# STM32_microcontroller_IOs.net
KiCad netlist of a schematic drawn in Altium Designer
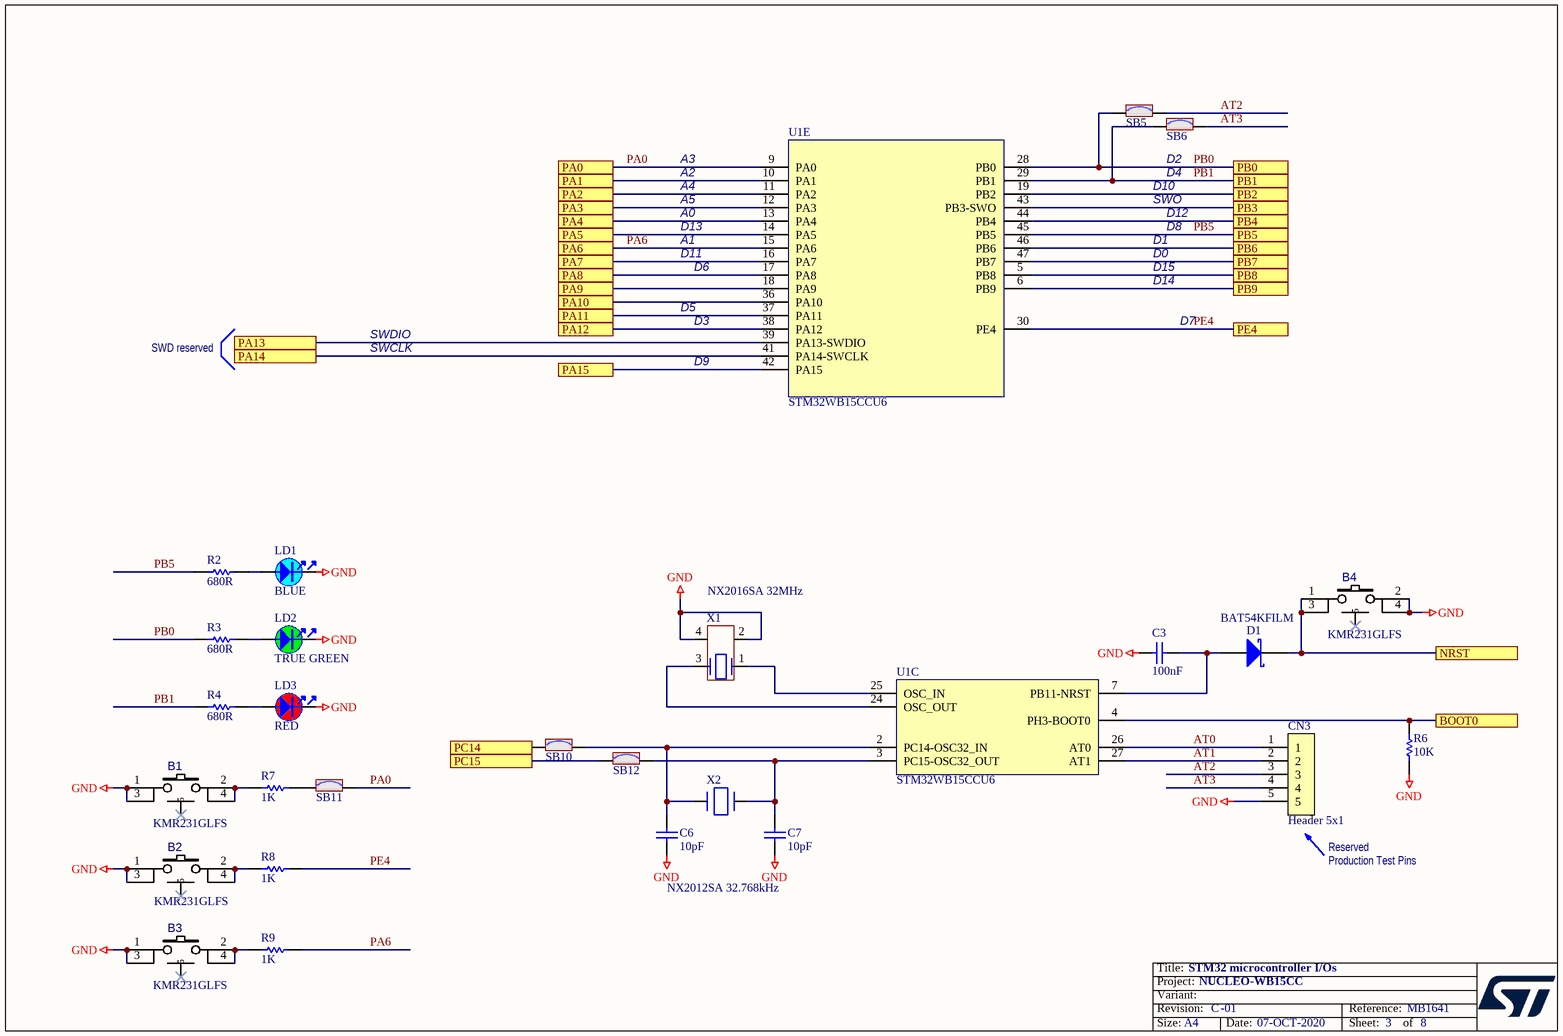
[diagram p0: STM32_microcontroller_IOs.SchDoc]

(export (version "E")
  (design (tool "Eeschema 10.0.6"))
  (components
    (comp (ref "B1")
      (value "KMR231GLFS")
      (footprint "SWI_C&K_Y78B23110FP__ITT_KMR231GLFS")
      (description "Microminiature Tact Switch for SMT - KMR 2 Series - 1.9 mm height")
      (fields (field (name "INTERNAL_PART_NUMBER") "MCD-01485") (field (name "MANUFACTURER") "C&K"))
      (libsource (lib "MCD_PARTS_database") (part "SW-PUSH-CMS_KMR2_BLACK"))
    )
    (comp (ref "B2")
      (value "KMR231GLFS")
      (footprint "SWI_C&K_Y78B23110FP__ITT_KMR231GLFS")
      (description "Microminiature Tact Switch for SMT - KMR 2 Series - 1.9 mm height")
      (fields (field (name "INTERNAL_PART_NUMBER") "MCD-01485") (field (name "MANUFACTURER") "C&K"))
      (libsource (lib "MCD_PARTS_database") (part "SW-PUSH-CMS_KMR2_BLACK"))
    )
    (comp (ref "B3")
      (value "KMR231GLFS")
      (footprint "SWI_C&K_Y78B23110FP__ITT_KMR231GLFS")
      (description "Microminiature Tact Switch for SMT - KMR 2 Series - 1.9 mm height")
      (fields (field (name "INTERNAL_PART_NUMBER") "MCD-01485") (field (name "MANUFACTURER") "C&K"))
      (libsource (lib "MCD_PARTS_database") (part "SW-PUSH-CMS_KMR2_BLACK"))
    )
    (comp (ref "B4")
      (value "KMR231GLFS")
      (footprint "SWI_C&K_Y78B23110FP__ITT_KMR231GLFS")
      (description "Microminiature Tact Switch for SMT - KMR 2 Series - 1.9 mm height")
      (fields (field (name "INTERNAL_PART_NUMBER") "MCD-01485") (field (name "MANUFACTURER") "C&K"))
      (libsource (lib "MCD_PARTS_database") (part "SW-PUSH-CMS_KMR2_BLACK"))
    )
    (comp (ref "C3")
      (value "100nF")
      (footprint "C0402")
      (description "Capacitor, MLCC, 100nF, 16V, X7R, +/-10%, 0402, T=0.5mm")
      (fields
        (field (name "INTERNAL_PART_NUMBER") "MCD-00006")
        (field (name "MANUFACTURER_PART_NUMBER") "CC0402KRX7R7BB104")
      )
      (libsource (lib "MCD_PARTS_database") (part "Capacitor"))
    )
    (comp (ref "C6")
      (value "10pF")
      (footprint "C0402")
      (description "Capacitor, MLCC, 10pF, 50V, NPO, +/-5%, 0402, T=0,5mm")
      (fields
        (field (name "INTERNAL_PART_NUMBER") "MCD-00015")
        (field (name "MANUFACTURER_PART_NUMBER") "CC0402JRNPO9BN100")
      )
      (libsource (lib "MCD_PARTS_database") (part "Capacitor"))
    )
    (comp (ref "C7")
      (value "10pF")
      (footprint "C0402")
      (description "Capacitor, MLCC, 10pF, 50V, NPO, +/-5%, 0402, T=0,5mm")
      (fields
        (field (name "INTERNAL_PART_NUMBER") "MCD-00015")
        (field (name "MANUFACTURER_PART_NUMBER") "CC0402JRNPO9BN100")
      )
      (libsource (lib "MCD_PARTS_database") (part "Capacitor"))
    )
    (comp (ref "CN3")
      (value "Header 5x1")
      (footprint "CON_SAMTEC_TSW-105-07-X-S")
      (description "Header, 5x1, 2,54mm, VR, TH, Height 5.84mm/2.54mm")
      (fields
        (field (name "INTERNAL_PART_NUMBER") "MCD-02060")
        (field (name "MANUFACTURER_PART_NUMBER") "TSW-105-07-G-S")
      )
      (libsource (lib "MCD_PARTS_database") (part "Header 5x1"))
    )
    (comp (ref "D1")
      (value "BAT54KFILM")
      (footprint "DIO_SOD523_1A_2K")
      (description "Small signal Schottky diodes")
      (fields
        (field (name "INTERNAL_PART_NUMBER") "MCD-01677")
        (field (name "MANUFACTURER") "STMICROELECTRONICS")
      )
      (libsource (lib "MCD_PARTS_database") (part "SCHOTTKY_1A_2K"))
    )
    (comp (ref "LD1")
      (value "BLUE")
      (footprint "LED_0603_VISHAY_VLMB1300-GS08_BLUE_1A2K_H0P8")
      (description "LED Blue, 0603 SMD, 3.3 V Forward Voltage")
      (fields
        (field (name "INTERNAL_PART_NUMBER") "MCD-00584")
        (field (name "MANUFACTURER_PART_NUMBER") "VLMB1300-GS08")
      )
      (libsource (lib "MCD_PARTS_database") (part "LED_blue"))
    )
    (comp (ref "LD2")
      (value "TRUE GREEN")
      (footprint "LED_0603_VISHAY_VLMTG1300-GS08_GREEN_1A2K_H0P8")
      (description "LED Green, 0603 SMD, Fw Voltage = 2.8V - 3.6V")
      (fields
        (field (name "INTERNAL_PART_NUMBER") "MCD-00589")
        (field (name "MANUFACTURER_PART_NUMBER") "VLMTG1300-GS08")
      )
      (libsource (lib "MCD_PARTS_database") (part "LED_green"))
    )
    (comp (ref "LD3")
      (value "RED")
      (footprint "LED_0603_VISHAY_VLMS1300-GS08_RED_1A2K_H0P8")
      (description "LED Red, 0603 SMD, 2V Forward Voltage")
      (fields
        (field (name "INTERNAL_PART_NUMBER") "MCD-00587")
        (field (name "MANUFACTURER_PART_NUMBER") "VLMS1300-GS08")
      )
      (libsource (lib "MCD_PARTS_database") (part "LED_red"))
    )
    (comp (ref "R2")
      (value "680R")
      (footprint "R0402")
      (description "Resistor,680R,0402,1%,1/16W")
      (fields
        (field (name "INTERNAL_PART_NUMBER") "MCD-00507")
        (field (name "MANUFACTURER_PART_NUMBER") "RC0402FR-07680RL")
      )
      (libsource (lib "MCD_PARTS_database") (part "Resistor"))
    )
    (comp (ref "R3")
      (value "680R")
      (footprint "R0402")
      (description "Resistor,680R,0402,1%,1/16W")
      (fields
        (field (name "INTERNAL_PART_NUMBER") "MCD-00507")
        (field (name "MANUFACTURER_PART_NUMBER") "RC0402FR-07680RL")
      )
      (libsource (lib "MCD_PARTS_database") (part "Resistor"))
    )
    (comp (ref "R4")
      (value "680R")
      (footprint "R0402")
      (description "Resistor,680R,0402,1%,1/16W")
      (fields
        (field (name "INTERNAL_PART_NUMBER") "MCD-00507")
        (field (name "MANUFACTURER_PART_NUMBER") "RC0402FR-07680RL")
      )
      (libsource (lib "MCD_PARTS_database") (part "Resistor"))
    )
    (comp (ref "R6")
      (value "10K")
      (footprint "R0402")
      (description "Resistor,10K,0402,1%,1/16W")
      (fields
        (field (name "INTERNAL_PART_NUMBER") "MCD-00053")
        (field (name "MANUFACTURER_PART_NUMBER") "RC0402FR-0710KL")
      )
      (libsource (lib "MCD_PARTS_database") (part "Resistor"))
    )
    (comp (ref "R7")
      (value "1K")
      (footprint "R0402")
      (description "Resistor,1K,0402,1%,1/16W")
      (fields
        (field (name "INTERNAL_PART_NUMBER") "MCD-00061")
        (field (name "MANUFACTURER_PART_NUMBER") "RC0402FR-071KL")
      )
      (libsource (lib "MCD_PARTS_database") (part "Resistor"))
    )
    (comp (ref "R8")
      (value "1K")
      (footprint "R0402")
      (description "Resistor,1K,0402,1%,1/16W")
      (fields
        (field (name "INTERNAL_PART_NUMBER") "MCD-00061")
        (field (name "MANUFACTURER_PART_NUMBER") "RC0402FR-071KL")
      )
      (libsource (lib "MCD_PARTS_database") (part "Resistor"))
    )
    (comp (ref "R9")
      (value "1K")
      (footprint "R0402")
      (description "Resistor,1K,0402,1%,1/16W")
      (fields
        (field (name "INTERNAL_PART_NUMBER") "MCD-00061")
        (field (name "MANUFACTURER_PART_NUMBER") "RC0402FR-071KL")
      )
      (libsource (lib "MCD_PARTS_database") (part "Resistor"))
    )
    (comp (ref "SB5")
      (value "SB_ON")
      (footprint "SOLDER-BRIDGE_R0402-0R")
      (description "Solder Bridge 0402 ON")
      (fields
        (field (name "INTERNAL_PART_NUMBER") "MCD-01618")
        (field (name "MANUFACTURER_PART_NUMBER") "RC0402JR-070RL")
      )
      (libsource (lib "MCD_PARTS_database") (part "SB_ON"))
    )
    (comp (ref "SB6")
      (value "SB_ON")
      (footprint "SOLDER-BRIDGE_R0402-0R")
      (description "Solder Bridge 0402 ON")
      (fields
        (field (name "INTERNAL_PART_NUMBER") "MCD-01618")
        (field (name "MANUFACTURER_PART_NUMBER") "RC0402JR-070RL")
      )
      (libsource (lib "MCD_PARTS_database") (part "SB_ON"))
    )
    (comp (ref "SB10")
      (value "SB_ON")
      (footprint "SOLDER-BRIDGE_R0402-0R")
      (description "Solder Bridge 0402 ON")
      (fields
        (field (name "INTERNAL_PART_NUMBER") "MCD-01618")
        (field (name "MANUFACTURER_PART_NUMBER") "RC0402JR-070RL")
      )
      (libsource (lib "MCD_PARTS_database") (part "SB_ON"))
    )
    (comp (ref "SB11")
      (value "SB_ON")
      (footprint "SOLDER-BRIDGE_R0402-0R")
      (description "Solder Bridge 0402 ON")
      (fields
        (field (name "INTERNAL_PART_NUMBER") "MCD-01618")
        (field (name "MANUFACTURER_PART_NUMBER") "RC0402JR-070RL")
      )
      (libsource (lib "MCD_PARTS_database") (part "SB_ON"))
    )
    (comp (ref "SB12")
      (value "SB_ON")
      (footprint "SOLDER-BRIDGE_R0402-0R")
      (description "Solder Bridge 0402 ON")
      (fields
        (field (name "INTERNAL_PART_NUMBER") "MCD-01618")
        (field (name "MANUFACTURER_PART_NUMBER") "RC0402JR-070RL")
      )
      (libsource (lib "MCD_PARTS_database") (part "SB_ON"))
    )
    (comp (ref "U1")
      (value "STM32WB15CCU6")
      (footprint "ICC_UFQFPN48-EPAD_7X7_H0P55_P050")
      (fields
        (field (name "INTERNAL_PART_NUMBER") "MCD-02058")
        (field (name "MANUFACTURER") "STMICROELECTRONICS")
        (field (name "Comment") "STM32WB15_QFN48")
      )
      (libsource (lib "MCD_PARTS_database") (part "STM32WB15_QFN48"))
    )
    (comp (ref "X1")
      (value "NX2016SA 32MHz")
      (footprint "CRY_NX2016SA_4P")
      (description "Crystal 32MHz, 8pF, +-10ppm, 60ohms max, SMD")
      (fields
        (field (name "INTERNAL_PART_NUMBER") "MCD-01446")
        (field (name "MANUFACTURER_PART_NUMBER") "NX2016SA 32MHz EXS00A-CS06654")
      )
      (libsource (lib "MCD_PARTS_database") (part "XTAL_4_PINS"))
    )
    (comp (ref "X2")
      (value "NX2012SA 32.768kHz")
      (footprint "CRY_NX2012SA_2P")
      (description "Crystal 32.768kHz, 7pF, +-20ppm, 80Kohms max, SMD")
      (fields
        (field (name "INTERNAL_PART_NUMBER") "MCD-01445")
        (field (name "MANUFACTURER_PART_NUMBER") "NX2012SA 32.768kHz EXS00A-MU00389")
      )
      (libsource (lib "MCD_PARTS_database") (part "XTAL_2_PINS"))
    )
  )
  (nets
    (net (code "1") (name "/AT0") (class "Default")
      (node (ref "CN3") (pin "1") (pinfunction "1_1") (pintype "passive"))
      (node (ref "U1") (pin "26") (pinfunction "AT0_26") (pintype "passive"))
    )
    (net (code "2") (name "/AT1") (class "Default")
      (node (ref "CN3") (pin "2") (pinfunction "2_2") (pintype "passive"))
      (node (ref "U1") (pin "27") (pinfunction "AT1_27") (pintype "passive"))
    )
    (net (code "3") (name "/AT2") (class "Default")
      (node (ref "CN3") (pin "3") (pinfunction "3_3") (pintype "passive"))
      (node (ref "SB5") (pin "2") (pinfunction "2_2") (pintype "passive"))
    )
    (net (code "4") (name "/AT3") (class "Default")
      (node (ref "CN3") (pin "4") (pinfunction "4_4") (pintype "passive"))
      (node (ref "SB6") (pin "2") (pinfunction "2_2") (pintype "passive"))
    )
    (net (code "5") (name "/BOOT0") (class "Default")
      (node (ref "R6") (pin "2") (pinfunction "2_2") (pintype "passive"))
      (node (ref "U1") (pin "4") (pinfunction "PH3-BOOT0_4") (pintype "passive"))
    )
    (net (code "6") (name "/NRST") (class "Default")
      (node (ref "B4") (pin "1") (pinfunction "1_1") (pintype "passive"))
      (node (ref "B4") (pin "3") (pinfunction "3_3") (pintype "passive"))
      (node (ref "D1") (pin "2") (pinfunction "K_2") (pintype "passive"))
    )
    (net (code "7") (name "/PA0") (class "Default")
      (node (ref "SB11") (pin "2") (pinfunction "2_2") (pintype "passive"))
      (node (ref "U1") (pin "9") (pinfunction "PA0_9") (pintype "passive"))
    )
    (net (code "8") (name "/PA1") (class "Default")
      (node (ref "U1") (pin "10") (pinfunction "PA1_10") (pintype "passive"))
    )
    (net (code "9") (name "/PA2") (class "Default")
      (node (ref "U1") (pin "11") (pinfunction "PA2_11") (pintype "passive"))
    )
    (net (code "10") (name "/PA3") (class "Default")
      (node (ref "U1") (pin "12") (pinfunction "PA3_12") (pintype "passive"))
    )
    (net (code "11") (name "/PA4") (class "Default")
      (node (ref "U1") (pin "13") (pinfunction "PA4_13") (pintype "passive"))
    )
    (net (code "12") (name "/PA5") (class "Default")
      (node (ref "U1") (pin "14") (pinfunction "PA5_14") (pintype "passive"))
    )
    (net (code "13") (name "/PA6") (class "Default")
      (node (ref "R9") (pin "2") (pinfunction "2_2") (pintype "passive"))
      (node (ref "U1") (pin "15") (pinfunction "PA6_15") (pintype "passive"))
    )
    (net (code "14") (name "/PA7") (class "Default")
      (node (ref "U1") (pin "16") (pinfunction "PA7_16") (pintype "passive"))
    )
    (net (code "15") (name "/PA8") (class "Default")
      (node (ref "U1") (pin "17") (pinfunction "PA8_17") (pintype "passive"))
    )
    (net (code "16") (name "/PA9") (class "Default")
      (node (ref "U1") (pin "18") (pinfunction "PA9_18") (pintype "passive"))
    )
    (net (code "17") (name "/PA10") (class "Default")
      (node (ref "U1") (pin "36") (pinfunction "PA10_36") (pintype "passive"))
    )
    (net (code "18") (name "/PA11") (class "Default")
      (node (ref "U1") (pin "37") (pinfunction "PA11_37") (pintype "passive"))
    )
    (net (code "19") (name "/PA12") (class "Default")
      (node (ref "U1") (pin "38") (pinfunction "PA12_38") (pintype "passive"))
    )
    (net (code "20") (name "/PA13") (class "Default")
      (node (ref "U1") (pin "39") (pinfunction "PA13-SWDIO_39") (pintype "passive"))
    )
    (net (code "21") (name "/PA14") (class "Default")
      (node (ref "U1") (pin "41") (pinfunction "PA14-SWCLK_41") (pintype "passive"))
    )
    (net (code "22") (name "/PA15") (class "Default")
      (node (ref "U1") (pin "42") (pinfunction "PA15_42") (pintype "passive"))
    )
    (net (code "23") (name "/PB0") (class "Default")
      (node (ref "R3") (pin "1") (pinfunction "1_1") (pintype "passive"))
      (node (ref "SB5") (pin "1") (pinfunction "1_1") (pintype "passive"))
      (node (ref "U1") (pin "28") (pinfunction "PB0_28") (pintype "passive"))
    )
    (net (code "24") (name "/PB1") (class "Default")
      (node (ref "R4") (pin "1") (pinfunction "1_1") (pintype "passive"))
      (node (ref "SB6") (pin "1") (pinfunction "1_1") (pintype "passive"))
      (node (ref "U1") (pin "29") (pinfunction "PB1_29") (pintype "passive"))
    )
    (net (code "25") (name "/PB2") (class "Default")
      (node (ref "U1") (pin "19") (pinfunction "PB2_19") (pintype "passive"))
    )
    (net (code "26") (name "/PB3") (class "Default")
      (node (ref "U1") (pin "43") (pinfunction "PB3-SWO_43") (pintype "passive"))
    )
    (net (code "27") (name "/PB4") (class "Default")
      (node (ref "U1") (pin "44") (pinfunction "PB4_44") (pintype "passive"))
    )
    (net (code "28") (name "/PB5") (class "Default")
      (node (ref "R2") (pin "1") (pinfunction "1_1") (pintype "passive"))
      (node (ref "U1") (pin "45") (pinfunction "PB5_45") (pintype "passive"))
    )
    (net (code "29") (name "/PB6") (class "Default")
      (node (ref "U1") (pin "46") (pinfunction "PB6_46") (pintype "passive"))
    )
    (net (code "30") (name "/PB7") (class "Default")
      (node (ref "U1") (pin "47") (pinfunction "PB7_47") (pintype "passive"))
    )
    (net (code "31") (name "/PB8") (class "Default")
      (node (ref "U1") (pin "5") (pinfunction "PB8_5") (pintype "passive"))
    )
    (net (code "32") (name "/PB9") (class "Default")
      (node (ref "U1") (pin "6") (pinfunction "PB9_6") (pintype "passive"))
    )
    (net (code "33") (name "/PC14") (class "Default")
      (node (ref "SB10") (pin "1") (pinfunction "1_1") (pintype "passive"))
    )
    (net (code "34") (name "/PC15") (class "Default")
      (node (ref "SB12") (pin "1") (pinfunction "1_1") (pintype "passive"))
    )
    (net (code "35") (name "/PE4") (class "Default")
      (node (ref "R8") (pin "2") (pinfunction "2_2") (pintype "passive"))
      (node (ref "U1") (pin "30") (pinfunction "PE4_30") (pintype "passive"))
    )
    (net (code "36") (name "GND") (class "Default")
      (node (ref "B1") (pin "1") (pinfunction "1_1") (pintype "passive"))
      (node (ref "B1") (pin "3") (pinfunction "3_3") (pintype "passive"))
      (node (ref "B2") (pin "1") (pinfunction "1_1") (pintype "passive"))
      (node (ref "B2") (pin "3") (pinfunction "3_3") (pintype "passive"))
      (node (ref "B3") (pin "1") (pinfunction "1_1") (pintype "passive"))
      (node (ref "B3") (pin "3") (pinfunction "3_3") (pintype "passive"))
      (node (ref "B4") (pin "2") (pinfunction "2_2") (pintype "passive"))
      (node (ref "B4") (pin "4") (pinfunction "4_4") (pintype "passive"))
      (node (ref "C3") (pin "1") (pinfunction "1_1") (pintype "passive"))
      (node (ref "C6") (pin "1") (pinfunction "1_1") (pintype "passive"))
      (node (ref "C7") (pin "1") (pinfunction "1_1") (pintype "passive"))
      (node (ref "CN3") (pin "5") (pinfunction "5_5") (pintype "passive"))
      (node (ref "LD1") (pin "2") (pintype "passive"))
      (node (ref "LD2") (pin "2") (pintype "passive"))
      (node (ref "LD3") (pin "2") (pintype "passive"))
      (node (ref "R6") (pin "1") (pinfunction "1_1") (pintype "passive"))
      (node (ref "X1") (pin "2") (pinfunction "2_2") (pintype "passive"))
      (node (ref "X1") (pin "4") (pinfunction "4_4") (pintype "passive"))
    )
    (net (code "37") (name "Net-(B1-Pad2)") (class "Default")
      (node (ref "B1") (pin "2") (pinfunction "2_2") (pintype "passive"))
      (node (ref "B1") (pin "4") (pinfunction "4_4") (pintype "passive"))
      (node (ref "R7") (pin "1") (pinfunction "1_1") (pintype "passive"))
    )
    (net (code "38") (name "Net-(B2-Pad2)") (class "Default")
      (node (ref "B2") (pin "2") (pinfunction "2_2") (pintype "passive"))
      (node (ref "B2") (pin "4") (pinfunction "4_4") (pintype "passive"))
      (node (ref "R8") (pin "1") (pinfunction "1_1") (pintype "passive"))
    )
    (net (code "39") (name "Net-(B3-Pad2)") (class "Default")
      (node (ref "B3") (pin "2") (pinfunction "2_2") (pintype "passive"))
      (node (ref "B3") (pin "4") (pinfunction "4_4") (pintype "passive"))
      (node (ref "R9") (pin "1") (pinfunction "1_1") (pintype "passive"))
    )
    (net (code "40") (name "Net-(D1-A)") (class "Default")
      (node (ref "C3") (pin "2") (pinfunction "2_2") (pintype "passive"))
      (node (ref "D1") (pin "1") (pinfunction "A_1") (pintype "passive"))
      (node (ref "U1") (pin "7") (pinfunction "PB11-NRST_7") (pintype "passive"))
    )
    (net (code "41") (name "Net-(LD1-Pad1)") (class "Default")
      (node (ref "LD1") (pin "1") (pintype "passive"))
      (node (ref "R2") (pin "2") (pinfunction "2_2") (pintype "passive"))
    )
    (net (code "42") (name "Net-(LD2-Pad1)") (class "Default")
      (node (ref "LD2") (pin "1") (pintype "passive"))
      (node (ref "R3") (pin "2") (pinfunction "2_2") (pintype "passive"))
    )
    (net (code "43") (name "Net-(LD3-Pad1)") (class "Default")
      (node (ref "LD3") (pin "1") (pintype "passive"))
      (node (ref "R4") (pin "2") (pinfunction "2_2") (pintype "passive"))
    )
    (net (code "44") (name "Net-(R7-Pad2)") (class "Default")
      (node (ref "R7") (pin "2") (pinfunction "2_2") (pintype "passive"))
      (node (ref "SB11") (pin "1") (pinfunction "1_1") (pintype "passive"))
    )
    (net (code "45") (name "Net-(U1C-OSC_IN)") (class "Default")
      (node (ref "U1") (pin "25") (pinfunction "OSC_IN_25") (pintype "passive"))
      (node (ref "X1") (pin "1") (pinfunction "1_1") (pintype "passive"))
    )
    (net (code "46") (name "Net-(U1C-OSC_OUT)") (class "Default")
      (node (ref "U1") (pin "24") (pinfunction "OSC_OUT_24") (pintype "passive"))
      (node (ref "X1") (pin "3") (pinfunction "3_3") (pintype "passive"))
    )
    (net (code "47") (name "Net-(U1C-PC14-OSC32_IN)") (class "Default")
      (node (ref "C6") (pin "2") (pinfunction "2_2") (pintype "passive"))
      (node (ref "SB10") (pin "2") (pinfunction "2_2") (pintype "passive"))
      (node (ref "U1") (pin "2") (pinfunction "PC14-OSC32_IN_2") (pintype "passive"))
      (node (ref "X2") (pin "1") (pinfunction "X1_1") (pintype "passive"))
    )
    (net (code "48") (name "Net-(U1C-PC15-OSC32_OUT)") (class "Default")
      (node (ref "C7") (pin "2") (pinfunction "2_2") (pintype "passive"))
      (node (ref "SB12") (pin "2") (pinfunction "2_2") (pintype "passive"))
      (node (ref "U1") (pin "3") (pinfunction "PC15-OSC32_OUT_3") (pintype "passive"))
      (node (ref "X2") (pin "2") (pinfunction "X2_2") (pintype "passive"))
    )
    (net (code "49") (name "unconnected-(B1-Pad5)") (class "Default")
      (node (ref "B1") (pin "5") (pinfunction "5_5") (pintype "passive+no_connect"))
    )
    (net (code "50") (name "unconnected-(B2-Pad5)") (class "Default")
      (node (ref "B2") (pin "5") (pinfunction "5_5") (pintype "passive+no_connect"))
    )
    (net (code "51") (name "unconnected-(B3-Pad5)") (class "Default")
      (node (ref "B3") (pin "5") (pinfunction "5_5") (pintype "passive+no_connect"))
    )
    (net (code "52") (name "unconnected-(B4-Pad5)") (class "Default")
      (node (ref "B4") (pin "5") (pinfunction "5_5") (pintype "passive+no_connect"))
    )
  )
)
